# DS18B20.net
KiCad netlist of a schematic drawn in EAGLE
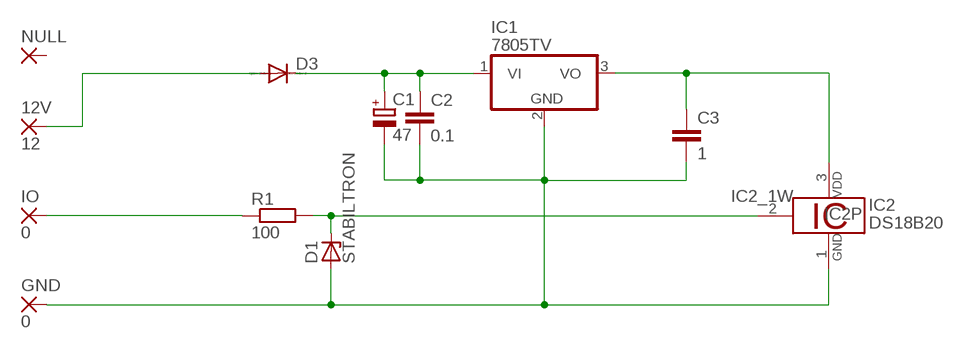
[diagram p0: schematic, sheet 1]

(export (version "E")
  (design (tool "Eeschema 10.0.6"))
  (components
    (comp (ref "12V")
      (value "12")
      (footprint "eagle-import:3,81_1,4")
      (libsource (lib "eagle-import") (part "3,81/1,4"))
    )
    (comp (ref "C1")
      (value "47")
      (footprint "eagle-import:E2,5-5")
      (libsource (lib "eagle-import") (part "CPOL-EUE2.5-5"))
    )
    (comp (ref "C2")
      (value "0.1")
      (footprint "eagle-import:C0805")
      (libsource (lib "eagle-import") (part "C-EUC0805"))
    )
    (comp (ref "C3")
      (value "1")
      (footprint "eagle-import:C0805")
      (libsource (lib "eagle-import") (part "C-EUC0805"))
    )
    (comp (ref "D1")
      (value "STABILTRON")
      (footprint "eagle-import:SOD80C")
      (libsource (lib "eagle-import") (part "ZENER-DIODESOD80C"))
    )
    (comp (ref "D3")
      (value "DIODE-SOD80C")
      (footprint "eagle-import:SOD80C")
      (libsource (lib "eagle-import") (part "DIODE-SOD80C"))
    )
    (comp (ref "GND")
      (value "0")
      (footprint "eagle-import:3,81_1,4")
      (libsource (lib "eagle-import") (part "3,81/1,4"))
    )
    (comp (ref "IC1")
      (value "7805TV")
      (footprint "eagle-import:TO220V")
      (libsource (lib "eagle-import") (part "78TV05"))
    )
    (comp (ref "IC2")
      (value "DS18B20")
      (footprint "eagle-import:TO92-")
      (libsource (lib "eagle-import") (part "DS18B20"))
    )
    (comp (ref "IO")
      (value "0")
      (footprint "eagle-import:3,81_1,4")
      (libsource (lib "eagle-import") (part "3,81/1,4"))
    )
    (comp (ref "NULL")
      (value "3,81/1,4")
      (footprint "eagle-import:3,81_1,4")
      (libsource (lib "eagle-import") (part "3,81/1,4"))
    )
    (comp (ref "R1")
      (value "100")
      (footprint "eagle-import:R0805")
      (libsource (lib "eagle-import") (part "R-EU_R0805"))
    )
  )
  (nets
    (net (code "1") (name "Net-(12V-P)") (class "Default")
      (node (ref "12V") (pin "1") (pinfunction "P_1") (pintype "passive"))
      (node (ref "D3") (pin "A") (pinfunction "A_A") (pintype "passive"))
    )
    (net (code "2") (name "Net-(GND-P)") (class "Default")
      (node (ref "C1") (pin "-") (pinfunction "-_-") (pintype "passive"))
      (node (ref "C2") (pin "2") (pinfunction "2_2") (pintype "passive"))
      (node (ref "C3") (pin "2") (pinfunction "2_2") (pintype "passive"))
      (node (ref "D1") (pin "A") (pinfunction "A_A") (pintype "passive"))
      (node (ref "GND") (pin "1") (pinfunction "P_1") (pintype "passive"))
      (node (ref "IC1") (pin "2") (pinfunction "GND_2") (pintype "passive"))
      (node (ref "IC2") (pin "1") (pinfunction "GND_1") (pintype "power_in"))
    )
    (net (code "3") (name "Net-(IC1-VI)") (class "Default")
      (node (ref "C1") (pin "+") (pinfunction "+_+") (pintype "passive"))
      (node (ref "C2") (pin "1") (pinfunction "1_1") (pintype "passive"))
      (node (ref "D3") (pin "C") (pinfunction "C_C") (pintype "passive"))
      (node (ref "IC1") (pin "1") (pinfunction "VI_1") (pintype "input"))
    )
    (net (code "4") (name "Net-(IC1-VO)") (class "Default")
      (node (ref "C3") (pin "1") (pinfunction "1_1") (pintype "passive"))
      (node (ref "IC1") (pin "3") (pinfunction "VO_3") (pintype "passive"))
      (node (ref "IC2") (pin "3") (pinfunction "VDD_3") (pintype "power_in"))
    )
    (net (code "5") (name "Net-(IC2C-1W)") (class "Default")
      (node (ref "D1") (pin "C") (pinfunction "C_C") (pintype "passive"))
      (node (ref "IC2") (pin "2") (pinfunction "1W_2") (pintype "power_in"))
      (node (ref "R1") (pin "2") (pinfunction "2_2") (pintype "passive"))
    )
    (net (code "6") (name "Net-(IO-P)") (class "Default")
      (node (ref "IO") (pin "1") (pinfunction "P_1") (pintype "passive"))
      (node (ref "R1") (pin "1") (pinfunction "1_1") (pintype "passive"))
    )
    (net (code "7") (name "unconnected-(NULL-P-Pad1)") (class "Default")
      (node (ref "NULL") (pin "1") (pinfunction "P_1") (pintype "passive"))
    )
  )
)
